# Enclosure_130x95_BP-R.net
KiCad netlist of a schematic drawn in EAGLE
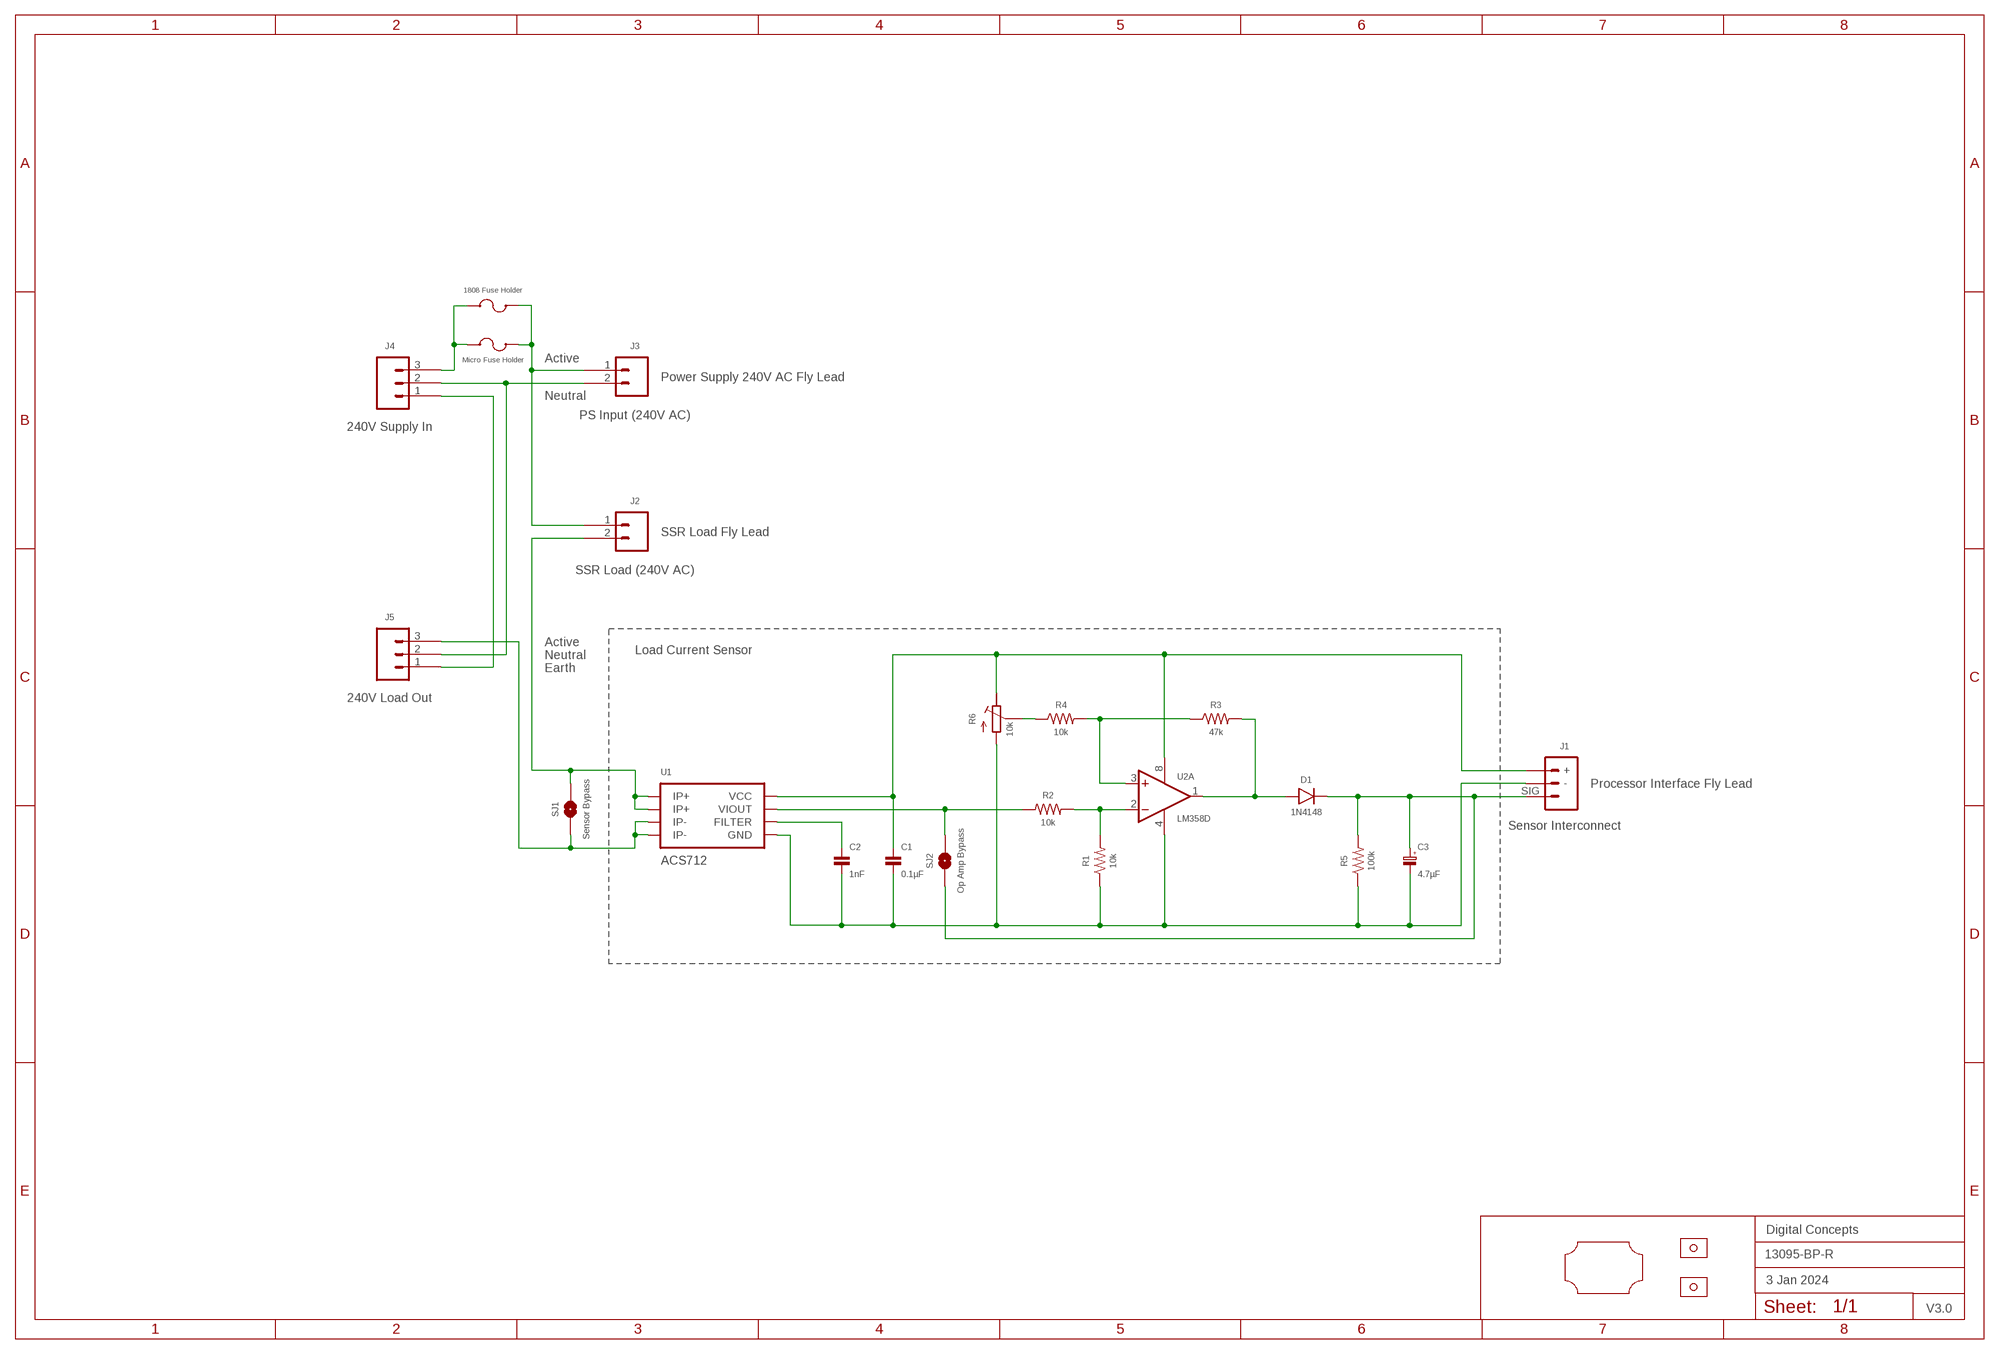
[diagram p0: schematic, sheet 1]

(export (version "E")
  (design (tool "Eeschema 10.0.6"))
  (components
    (comp (ref "C1")
      (value "0.1µF")
      (footprint "eagle-import:C0805")
      (libsource (lib "eagle-import") (part "CAPACITOR-0805"))
    )
    (comp (ref "C2")
      (value "1nF")
      (footprint "eagle-import:C0805")
      (libsource (lib "eagle-import") (part "CAPACITOR-0805"))
    )
    (comp (ref "C3")
      (value "4.7µF")
      (footprint "eagle-import:C1206-POLARISED")
      (libsource (lib "eagle-import") (part "CAPACITOR-1206-TANTALUM"))
    )
    (comp (ref "D1")
      (value "1N4148")
      (footprint "eagle-import:SOD-323")
      (libsource (lib "eagle-import") (part "DIODE-1N4148-SOD323"))
    )
    (comp (ref "F2")
      (value "1808 Fuse Holder")
      (footprint "eagle-import:FUSE-HOLDER-1808")
      (libsource (lib "eagle-import") (part "FUSE-HOLDER-1808"))
    )
    (comp (ref "J1")
      (value "Sensor Interconnect")
      (footprint "eagle-import:JST-PH2.0-3-HORIZONTAL-SIG")
      (libsource (lib "eagle-import") (part "JST-PH2.0-3-HORIZONTAL"))
    )
    (comp (ref "J2")
      (value "SSR Load (240V AC)")
      (footprint "eagle-import:TERMINAL-SCREW-2P")
      (libsource (lib "eagle-import") (part "TERMINAL_SCREW_2P_VERTICAL"))
    )
    (comp (ref "J3")
      (value "PS Input (240V AC)")
      (footprint "eagle-import:JST-XH2.4-2-HORIZONTAL")
      (libsource (lib "eagle-import") (part "JST-XH2.54-2-HORIZONTAL"))
    )
    (comp (ref "J4")
      (value "240V Supply In")
      (footprint "eagle-import:TERMINAL-SCREW-3P")
      (libsource (lib "eagle-import") (part "TERMINAL_SCREW_3P_VERTICAL"))
    )
    (comp (ref "J5")
      (value "240V Load Out")
      (footprint "eagle-import:TERMINAL-SCREW-3P")
      (libsource (lib "eagle-import") (part "TERMINAL_SCREW_3P_VERTICAL"))
    )
    (comp (ref "R1")
      (value "10k")
      (footprint "eagle-import:R0805")
      (libsource (lib "eagle-import") (part "RESISTORR0805"))
    )
    (comp (ref "R2")
      (value "10k")
      (footprint "eagle-import:R0805")
      (libsource (lib "eagle-import") (part "RESISTORR0805"))
    )
    (comp (ref "R3")
      (value "47k")
      (footprint "eagle-import:R0805")
      (libsource (lib "eagle-import") (part "RESISTORR0805"))
    )
    (comp (ref "R4")
      (value "10k")
      (footprint "eagle-import:R0805")
      (libsource (lib "eagle-import") (part "RESISTORR0805"))
    )
    (comp (ref "R5")
      (value "100k")
      (footprint "eagle-import:R0805")
      (libsource (lib "eagle-import") (part "RESISTORR0805"))
    )
    (comp (ref "R6")
      (value "10k")
      (footprint "eagle-import:RTRIM3386P")
      (libsource (lib "eagle-import") (part "RESISTOR-TRIMM-3386P"))
    )
    (comp (ref "SJ1")
      (value "Sensor Bypass")
      (footprint "eagle-import:SJ")
      (libsource (lib "eagle-import") (part "SJ"))
    )
    (comp (ref "SJ2")
      (value "Op Amp Bypass")
      (footprint "eagle-import:SJ")
      (libsource (lib "eagle-import") (part "SJ"))
    )
    (comp (ref "U$1")
      (value "PCB-OUTLINE-130X95-MAX-RC-H3")
      (footprint "eagle-import:PROTO-130X95-OUTLINE-MAX-RC-H3")
      (libsource (lib "eagle-import") (part "PCB-OUTLINE-130X95-MAX-RC-H3"))
    )
    (comp (ref "U$2")
      (value "Micro Fuse Holder")
      (footprint "eagle-import:FUSE-HOLDER-MICRO")
      (libsource (lib "eagle-import") (part "FUSE-HOLDER"))
    )
    (comp (ref "U$4")
      (value "STRAIN-RELIEF-SADDLE")
      (footprint "eagle-import:STRAIN-RELIEF-SADDLE")
      (libsource (lib "eagle-import") (part "STRAIN-RELIEF-SADDLE"))
    )
    (comp (ref "U$5")
      (value "STRAIN-RELIEF-SADDLE")
      (footprint "eagle-import:STRAIN-RELIEF-SADDLE")
      (libsource (lib "eagle-import") (part "STRAIN-RELIEF-SADDLE"))
    )
    (comp (ref "U1")
      (value "ACS712")
      (footprint "eagle-import:SOP-8")
      (libsource (lib "eagle-import") (part "ACS712"))
    )
    (comp (ref "U2")
      (value "LM358D")
      (footprint "eagle-import:SOP-8")
      (libsource (lib "eagle-import") (part "LM358D"))
    )
  )
  (nets
    (net (code "1") (name "Net-(C3-+)") (class "Default")
      (node (ref "C3") (pin "1") (pinfunction "+_1") (pintype "passive"))
      (node (ref "D1") (pin "C") (pinfunction "1_C") (pintype "bidirectional"))
      (node (ref "J1") (pin "SIG") (pinfunction "SIG_SIG") (pintype "bidirectional"))
      (node (ref "R5") (pin "2") (pinfunction "2_2") (pintype "passive"))
      (node (ref "SJ2") (pin "1") (pinfunction "1_1") (pintype "passive"))
    )
    (net (code "2") (name "Net-(C3--)") (class "Default")
      (node (ref "C1") (pin "2") (pinfunction "2_2") (pintype "passive"))
      (node (ref "C2") (pin "2") (pinfunction "2_2") (pintype "passive"))
      (node (ref "C3") (pin "2") (pinfunction "-_2") (pintype "passive"))
      (node (ref "J1") (pin "-") (pinfunction "-_-") (pintype "power_in"))
      (node (ref "R1") (pin "1") (pinfunction "1_1") (pintype "passive"))
      (node (ref "R5") (pin "1") (pinfunction "1_1") (pintype "passive"))
      (node (ref "R6") (pin "3") (pinfunction "A_3") (pintype "passive"))
      (node (ref "U1") (pin "5") (pinfunction "GND_5") (pintype "power_in"))
      (node (ref "U2") (pin "4") (pinfunction "V-_4") (pintype "power_in"))
    )
    (net (code "3") (name "Net-(D1-2)") (class "Default")
      (node (ref "D1") (pin "A") (pinfunction "2_A") (pintype "bidirectional"))
      (node (ref "R3") (pin "2") (pinfunction "2_2") (pintype "passive"))
      (node (ref "U2") (pin "1") (pinfunction "OUT_1") (pintype "output"))
    )
    (net (code "4") (name "Net-(F2-1)") (class "Default")
      (node (ref "F2") (pin "P$1") (pinfunction "1_P$1") (pintype "passive"))
      (node (ref "J4") (pin "3") (pinfunction "3_3") (pintype "passive"))
      (node (ref "U$2") (pin "P$1") (pinfunction "1_P$1") (pintype "passive"))
      (node (ref "U$2") (pin "P$2") (pinfunction "1_P$2") (pintype "passive"))
    )
    (net (code "5") (name "Net-(F2-2)") (class "Default")
      (node (ref "F2") (pin "P$2") (pinfunction "2_P$2") (pintype "passive"))
      (node (ref "J2") (pin "1") (pinfunction "1_1") (pintype "passive"))
      (node (ref "J3") (pin "1") (pinfunction "1_1") (pintype "passive"))
      (node (ref "U$2") (pin "P$3") (pinfunction "2_P$3") (pintype "passive"))
      (node (ref "U$2") (pin "P$4") (pinfunction "2_P$4") (pintype "passive"))
    )
    (net (code "6") (name "Net-(J2-Pad2)") (class "Default")
      (node (ref "J2") (pin "2") (pinfunction "2_2") (pintype "passive"))
      (node (ref "SJ1") (pin "2") (pinfunction "2_2") (pintype "passive"))
      (node (ref "U1") (pin "1") (pinfunction "IP+_1") (pintype "bidirectional"))
      (node (ref "U1") (pin "2") (pinfunction "IP+_2") (pintype "bidirectional"))
    )
    (net (code "7") (name "Net-(J3-Pad2)") (class "Default")
      (node (ref "J3") (pin "2") (pinfunction "2_2") (pintype "passive"))
      (node (ref "J4") (pin "2") (pinfunction "2_2") (pintype "passive"))
      (node (ref "J5") (pin "2") (pinfunction "2_2") (pintype "passive"))
    )
    (net (code "8") (name "Net-(J4-Pad1)") (class "Default")
      (node (ref "J4") (pin "1") (pinfunction "1_1") (pintype "passive"))
      (node (ref "J5") (pin "1") (pinfunction "1_1") (pintype "passive"))
    )
    (net (code "9") (name "Net-(J5-Pad3)") (class "Default")
      (node (ref "J5") (pin "3") (pinfunction "3_3") (pintype "passive"))
      (node (ref "SJ1") (pin "1") (pinfunction "1_1") (pintype "passive"))
      (node (ref "U1") (pin "3") (pinfunction "IP-_3") (pintype "bidirectional"))
      (node (ref "U1") (pin "4") (pinfunction "IP-_4") (pintype "bidirectional"))
    )
    (net (code "10") (name "Net-(R6-E)") (class "Default")
      (node (ref "C1") (pin "1") (pinfunction "1_1") (pintype "passive"))
      (node (ref "J1") (pin "+") (pinfunction "+_+") (pintype "power_in"))
      (node (ref "R6") (pin "1") (pinfunction "E_1") (pintype "passive"))
      (node (ref "U1") (pin "8") (pinfunction "VCC_8") (pintype "power_in"))
      (node (ref "U2") (pin "8") (pinfunction "V+_8") (pintype "power_in"))
    )
    (net (code "11") (name "Net-(R6-S)") (class "Default")
      (node (ref "R4") (pin "1") (pinfunction "1_1") (pintype "passive"))
      (node (ref "R6") (pin "2") (pinfunction "S_2") (pintype "passive"))
    )
    (net (code "12") (name "Net-(U1-FILTER)") (class "Default")
      (node (ref "C2") (pin "1") (pinfunction "1_1") (pintype "passive"))
      (node (ref "U1") (pin "6") (pinfunction "FILTER_6") (pintype "bidirectional"))
    )
    (net (code "13") (name "Net-(U1-VIOUT)") (class "Default")
      (node (ref "R2") (pin "1") (pinfunction "1_1") (pintype "passive"))
      (node (ref "SJ2") (pin "2") (pinfunction "2_2") (pintype "passive"))
      (node (ref "U1") (pin "7") (pinfunction "VIOUT_7") (pintype "bidirectional"))
    )
    (net (code "14") (name "Net-(U2A-+IN)") (class "Default")
      (node (ref "R3") (pin "1") (pinfunction "1_1") (pintype "passive"))
      (node (ref "R4") (pin "2") (pinfunction "2_2") (pintype "passive"))
      (node (ref "U2") (pin "3") (pinfunction "+IN_3") (pintype "input"))
    )
    (net (code "15") (name "Net-(U2A--IN)") (class "Default")
      (node (ref "R1") (pin "2") (pinfunction "2_2") (pintype "passive"))
      (node (ref "R2") (pin "2") (pinfunction "2_2") (pintype "passive"))
      (node (ref "U2") (pin "2") (pinfunction "-IN_2") (pintype "input"))
    )
  )
)
